# fonteSCH.net
KiCad netlist of a schematic drawn in EAGLE
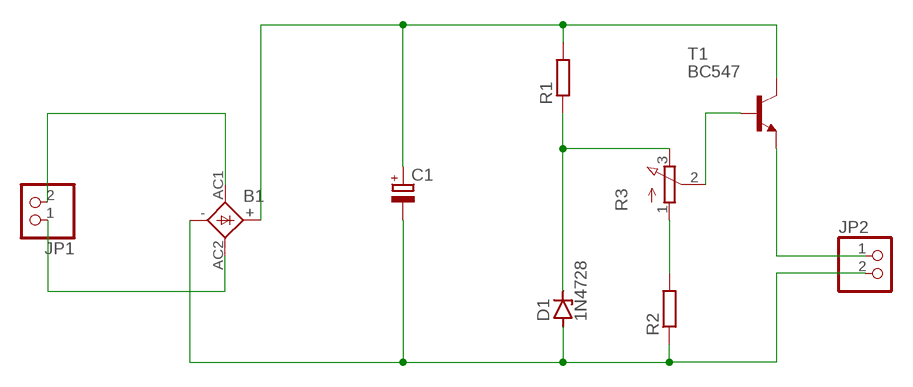
[diagram p0: schematic, sheet 1]

(export (version "E")
  (design (tool "Eeschema 10.0.6"))
  (components
    (comp (ref "B1")
      (value "1KAB")
      (footprint "eagle-import:1KAB")
      (libsource (lib "eagle-import") (part "1KAB"))
    )
    (comp (ref "C1")
      (value "CPOL-EUE5-10.5")
      (footprint "eagle-import:E5-10,5")
      (libsource (lib "eagle-import") (part "CPOL-EUE5-10.5"))
    )
    (comp (ref "D1")
      (value "1N4728")
      (footprint "eagle-import:DO41Z10")
      (libsource (lib "eagle-import") (part "1N4728"))
    )
    (comp (ref "JP1")
      (value "PINHD-1X2")
      (footprint "eagle-import:1X02")
      (libsource (lib "eagle-import") (part "PINHD-1X2"))
    )
    (comp (ref "JP2")
      (value "PINHD-1X2")
      (footprint "eagle-import:1X02")
      (libsource (lib "eagle-import") (part "PINHD-1X2"))
    )
    (comp (ref "R1")
      (value "R-EU_0207/10")
      (footprint "eagle-import:0207_10")
      (libsource (lib "eagle-import") (part "R-EU_0207/10"))
    )
    (comp (ref "R2")
      (value "R-EU_0207/10")
      (footprint "eagle-import:0207_10")
      (libsource (lib "eagle-import") (part "R-EU_0207/10"))
    )
    (comp (ref "R3")
      (value "3RP/1610N")
      (footprint "eagle-import:3RP_1610N")
      (libsource (lib "eagle-import") (part "3RP/1610N"))
    )
    (comp (ref "T1")
      (value "BC547")
      (footprint "eagle-import:TO92")
      (libsource (lib "eagle-import") (part "BC547"))
    )
  )
  (nets
    (net (code "1") (name "Net-(B1-Pad-)") (class "Default")
      (node (ref "B1") (pin "-") (pinfunction "-_-") (pintype "passive"))
      (node (ref "C1") (pin "-") (pinfunction "-_-") (pintype "passive"))
      (node (ref "D1") (pin "A") (pinfunction "A_A") (pintype "passive"))
      (node (ref "JP2") (pin "2") (pinfunction "2_2") (pintype "passive"))
      (node (ref "R2") (pin "1") (pinfunction "1_1") (pintype "passive"))
    )
    (net (code "2") (name "Net-(B1-PadAC1)") (class "Default")
      (node (ref "B1") (pin "AC1") (pinfunction "AC1_AC1") (pintype "passive"))
      (node (ref "JP1") (pin "2") (pinfunction "2_2") (pintype "passive"))
    )
    (net (code "3") (name "Net-(B1-PadAC2)") (class "Default")
      (node (ref "B1") (pin "AC2") (pinfunction "AC2_AC2") (pintype "passive"))
      (node (ref "JP1") (pin "1") (pinfunction "1_1") (pintype "passive"))
    )
    (net (code "4") (name "Net-(R3-A)") (class "Default")
      (node (ref "R2") (pin "2") (pinfunction "2_2") (pintype "passive"))
      (node (ref "R3") (pin "1") (pinfunction "A_1") (pintype "passive"))
    )
    (net (code "5") (name "Net-(R3-E)") (class "Default")
      (node (ref "D1") (pin "C") (pinfunction "C_C") (pintype "passive"))
      (node (ref "R1") (pin "1") (pinfunction "1_1") (pintype "passive"))
      (node (ref "R3") (pin "3") (pinfunction "E_3") (pintype "passive"))
    )
    (net (code "6") (name "Net-(R3-S)") (class "Default")
      (node (ref "R3") (pin "2") (pinfunction "S_2") (pintype "passive"))
      (node (ref "T1") (pin "2") (pinfunction "B_2") (pintype "passive"))
    )
    (net (code "7") (name "Net-(T1-C)") (class "Default")
      (node (ref "B1") (pin "+") (pinfunction "+_+") (pintype "passive"))
      (node (ref "C1") (pin "+") (pinfunction "+_+") (pintype "passive"))
      (node (ref "R1") (pin "2") (pinfunction "2_2") (pintype "passive"))
      (node (ref "T1") (pin "3") (pinfunction "C_3") (pintype "passive"))
    )
    (net (code "8") (name "Net-(T1-E)") (class "Default")
      (node (ref "JP2") (pin "1") (pinfunction "1_1") (pintype "passive"))
      (node (ref "T1") (pin "1") (pinfunction "E_1") (pintype "passive"))
    )
  )
)
